# PBC-1.net
KiCad netlist of a schematic drawn in EAGLE
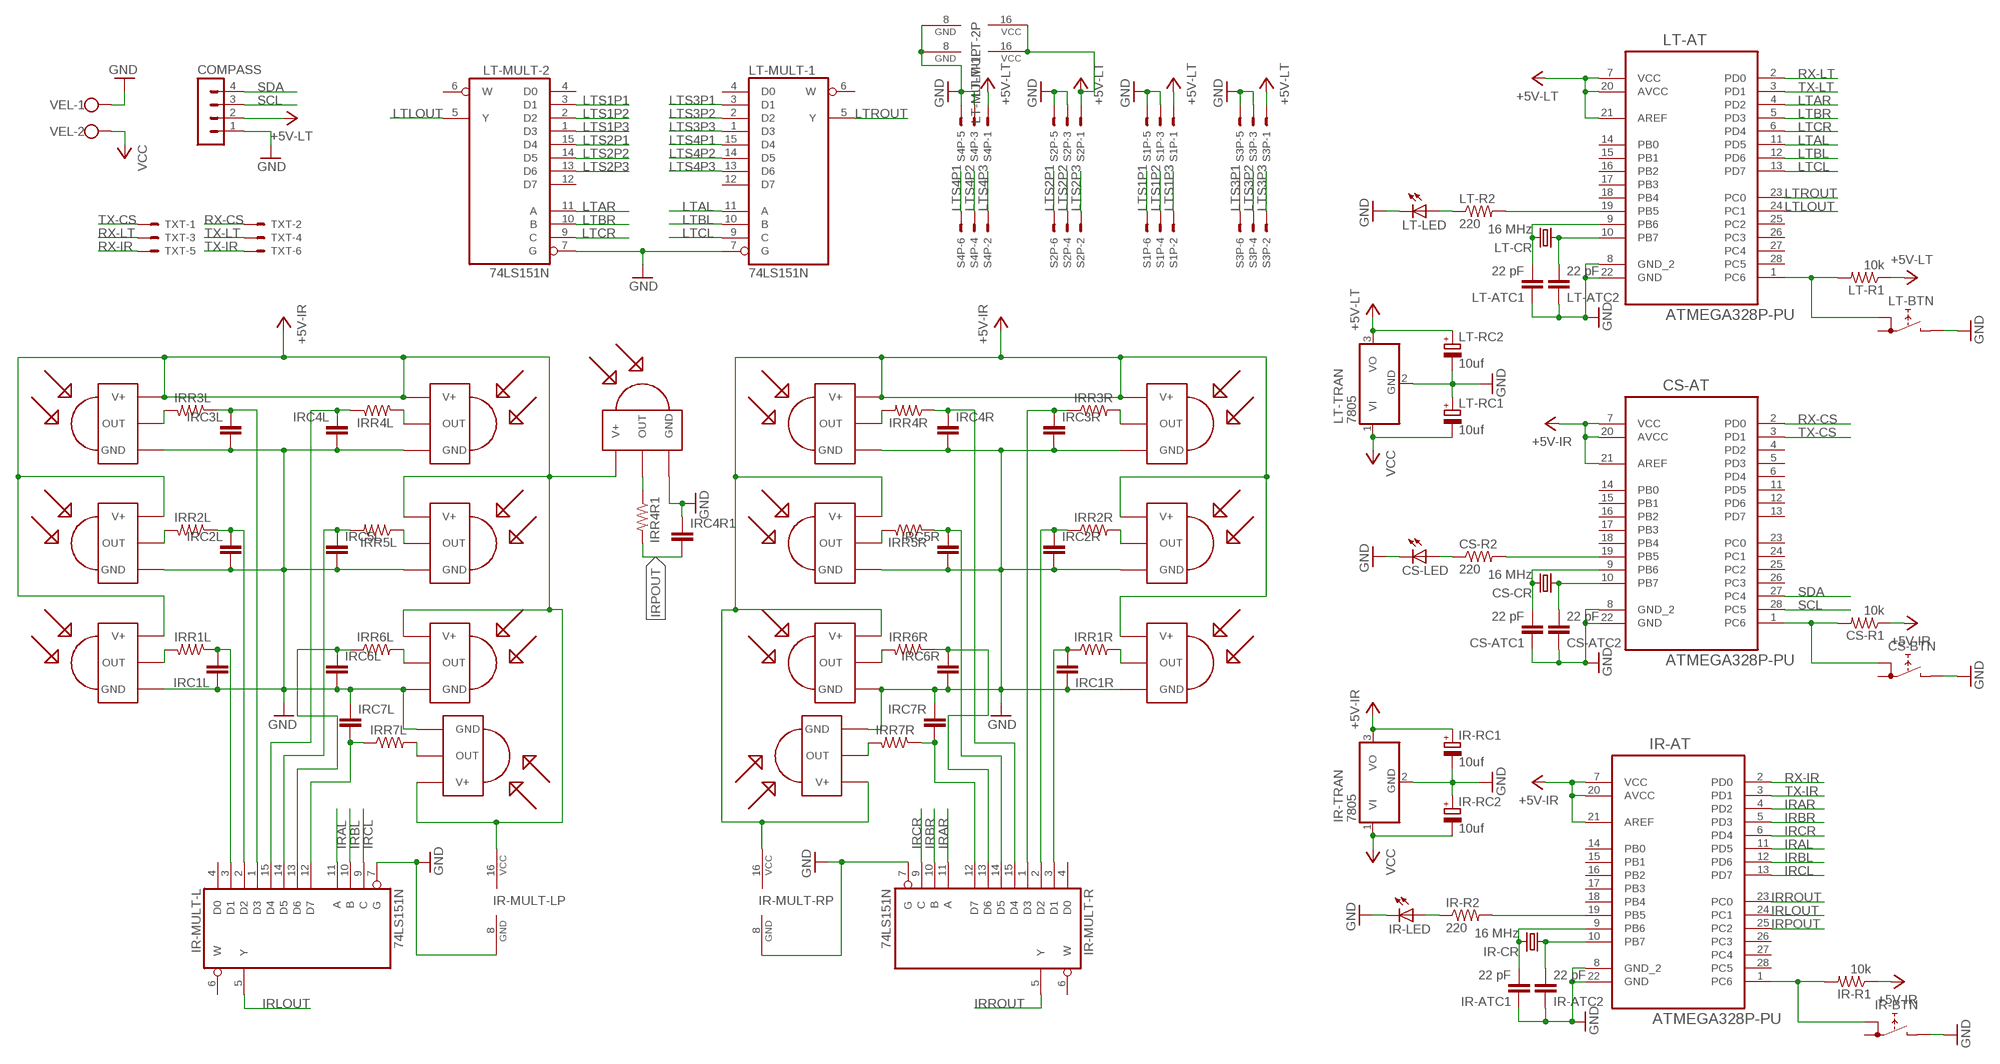
[diagram p0: schematic, sheet 1]

(export (version "E")
  (design (tool "Eeschema 10.0.6"))
  (components
    (comp (ref "COMPASS")
      (value "MA04-1")
      (footprint "eagle-import:MA04-1")
      (libsource (lib "eagle-import") (part "MA04-1"))
    )
    (comp (ref "CS-AT")
      (value "ATMEGA328P-PU")
      (footprint "eagle-import:DIP254P762X457-28")
      (libsource (lib "eagle-import") (part "ATMEGA328P-PU"))
    )
    (comp (ref "CS-ATC1")
      (value "22 pF")
      (footprint "eagle-import:C2.5-3")
      (libsource (lib "eagle-import") (part "C2,5-3"))
    )
    (comp (ref "CS-ATC2")
      (value "22 pF")
      (footprint "eagle-import:C2.5-3")
      (libsource (lib "eagle-import") (part "C2,5-3"))
    )
    (comp (ref "CS-BTN")
      (value "RDT1034")
      (footprint "eagle-import:RDT1034")
      (libsource (lib "eagle-import") (part "RDT1034"))
    )
    (comp (ref "CS-CR")
      (value "16 MHz")
      (footprint "eagle-import:HC49U70")
      (libsource (lib "eagle-import") (part "CRYSTALHC49U70"))
    )
    (comp (ref "CS-LED")
      (value "LED5MM")
      (footprint "eagle-import:LED5MM")
      (libsource (lib "eagle-import") (part "LED5MM"))
    )
    (comp (ref "CS-R1")
      (value "10k")
      (footprint "eagle-import:0204_7")
      (libsource (lib "eagle-import") (part "R-US_0204/7"))
    )
    (comp (ref "CS-R2")
      (value "220")
      (footprint "eagle-import:0204_7")
      (libsource (lib "eagle-import") (part "R-US_0204/7"))
    )
    (comp (ref "IR-AT")
      (value "ATMEGA328P-PU")
      (footprint "eagle-import:DIP254P762X457-28")
      (libsource (lib "eagle-import") (part "ATMEGA328P-PU"))
    )
    (comp (ref "IR-ATC1")
      (value "22 pF")
      (footprint "eagle-import:C2.5-3")
      (libsource (lib "eagle-import") (part "C2,5-3"))
    )
    (comp (ref "IR-ATC2")
      (value "22 pF")
      (footprint "eagle-import:C2.5-3")
      (libsource (lib "eagle-import") (part "C2,5-3"))
    )
    (comp (ref "IR-BTN")
      (value "RDT1034")
      (footprint "eagle-import:RDT1034")
      (libsource (lib "eagle-import") (part "RDT1034"))
    )
    (comp (ref "IR-CR")
      (value "16 MHz")
      (footprint "eagle-import:HC49U70")
      (libsource (lib "eagle-import") (part "CRYSTALHC49U70"))
    )
    (comp (ref "IR-LED")
      (value "LED5MM")
      (footprint "eagle-import:LED5MM")
      (libsource (lib "eagle-import") (part "LED5MM"))
    )
    (comp (ref "IR-MULT-L")
      (value "74LS151N")
      (footprint "eagle-import:DIL16")
      (libsource (lib "eagle-import") (part "74151NLS"))
    )
    (comp (ref "IR-MULT-R")
      (value "74LS151N")
      (footprint "eagle-import:DIL16")
      (libsource (lib "eagle-import") (part "74151NLS"))
    )
    (comp (ref "IR-R1")
      (value "10k")
      (footprint "eagle-import:0204_7")
      (libsource (lib "eagle-import") (part "R-US_0204/7"))
    )
    (comp (ref "IR-R2")
      (value "220")
      (footprint "eagle-import:0204_7")
      (libsource (lib "eagle-import") (part "R-US_0204/7"))
    )
    (comp (ref "IR-RC1")
      (value "10uf")
      (footprint "eagle-import:TT5D9")
      (libsource (lib "eagle-import") (part "CPOL-EUTT5D9"))
    )
    (comp (ref "IR-RC2")
      (value "10uf")
      (footprint "eagle-import:TT5D9")
      (libsource (lib "eagle-import") (part "CPOL-EUTT5D9"))
    )
    (comp (ref "IR-TRAN")
      (value "7805")
      (footprint "eagle-import:TO220H")
      (libsource (lib "eagle-import") (part "78T05"))
    )
    (comp (ref "IRC1L")
      (value "C-EU025-024X044")
      (footprint "eagle-import:C025-024X044")
      (libsource (lib "eagle-import") (part "C-EU025-024X044"))
    )
    (comp (ref "IRC1R")
      (value "C-EU025-024X044")
      (footprint "eagle-import:C025-024X044")
      (libsource (lib "eagle-import") (part "C-EU025-024X044"))
    )
    (comp (ref "IRC2L")
      (value "C-EU025-024X044")
      (footprint "eagle-import:C025-024X044")
      (libsource (lib "eagle-import") (part "C-EU025-024X044"))
    )
    (comp (ref "IRC2R")
      (value "C-EU025-024X044")
      (footprint "eagle-import:C025-024X044")
      (libsource (lib "eagle-import") (part "C-EU025-024X044"))
    )
    (comp (ref "IRC3L")
      (value "C-EU025-024X044")
      (footprint "eagle-import:C025-024X044")
      (libsource (lib "eagle-import") (part "C-EU025-024X044"))
    )
    (comp (ref "IRC3R")
      (value "C-EU025-024X044")
      (footprint "eagle-import:C025-024X044")
      (libsource (lib "eagle-import") (part "C-EU025-024X044"))
    )
    (comp (ref "IRC4L")
      (value "C-EU025-024X044")
      (footprint "eagle-import:C025-024X044")
      (libsource (lib "eagle-import") (part "C-EU025-024X044"))
    )
    (comp (ref "IRC4R")
      (value "C-EU025-024X044")
      (footprint "eagle-import:C025-024X044")
      (libsource (lib "eagle-import") (part "C-EU025-024X044"))
    )
    (comp (ref "IRC4R1")
      (value "C-EU025-024X044")
      (footprint "eagle-import:C025-024X044")
      (libsource (lib "eagle-import") (part "C-EU025-024X044"))
    )
    (comp (ref "IRC5L")
      (value "C-EU025-024X044")
      (footprint "eagle-import:C025-024X044")
      (libsource (lib "eagle-import") (part "C-EU025-024X044"))
    )
    (comp (ref "IRC5R")
      (value "C-EU025-024X044")
      (footprint "eagle-import:C025-024X044")
      (libsource (lib "eagle-import") (part "C-EU025-024X044"))
    )
    (comp (ref "IRC6L")
      (value "C-EU025-024X044")
      (footprint "eagle-import:C025-024X044")
      (libsource (lib "eagle-import") (part "C-EU025-024X044"))
    )
    (comp (ref "IRC6R")
      (value "C-EU025-024X044")
      (footprint "eagle-import:C025-024X044")
      (libsource (lib "eagle-import") (part "C-EU025-024X044"))
    )
    (comp (ref "IRC7L")
      (value "C-EU025-024X044")
      (footprint "eagle-import:C025-024X044")
      (libsource (lib "eagle-import") (part "C-EU025-024X044"))
    )
    (comp (ref "IRC7R")
      (value "C-EU025-024X044")
      (footprint "eagle-import:C025-024X044")
      (libsource (lib "eagle-import") (part "C-EU025-024X044"))
    )
    (comp (ref "IRD1L")
      (value "TSOP2240")
      (footprint "eagle-import:TSOP18XX")
      (libsource (lib "eagle-import") (part "TSOP1840"))
    )
    (comp (ref "IRD1R")
      (value "TSOP2240")
      (footprint "eagle-import:TSOP18XX")
      (libsource (lib "eagle-import") (part "TSOP1840"))
    )
    (comp (ref "IRD2L")
      (value "TSOP2240")
      (footprint "eagle-import:TSOP18XX")
      (libsource (lib "eagle-import") (part "TSOP1840"))
    )
    (comp (ref "IRD2R")
      (value "TSOP2240")
      (footprint "eagle-import:TSOP18XX")
      (libsource (lib "eagle-import") (part "TSOP1840"))
    )
    (comp (ref "IRD3L")
      (value "TSOP2240")
      (footprint "eagle-import:TSOP18XX")
      (libsource (lib "eagle-import") (part "TSOP1840"))
    )
    (comp (ref "IRD3R")
      (value "TSOP1840")
      (footprint "eagle-import:TSOP18XX")
      (libsource (lib "eagle-import") (part "TSOP1840"))
    )
    (comp (ref "IRD4L")
      (value "TSOP2240")
      (footprint "eagle-import:TSOP18XX")
      (libsource (lib "eagle-import") (part "TSOP1840"))
    )
    (comp (ref "IRD4R")
      (value "TSOP2240")
      (footprint "eagle-import:TSOP18XX")
      (libsource (lib "eagle-import") (part "TSOP1840"))
    )
    (comp (ref "IRD5L")
      (value "TSOP2240")
      (footprint "eagle-import:TSOP18XX")
      (libsource (lib "eagle-import") (part "TSOP1840"))
    )
    (comp (ref "IRD5R")
      (value "TSOP2240")
      (footprint "eagle-import:TSOP18XX")
      (libsource (lib "eagle-import") (part "TSOP1840"))
    )
    (comp (ref "IRD6L")
      (value "TSOP2240")
      (footprint "eagle-import:TSOP18XX")
      (libsource (lib "eagle-import") (part "TSOP1840"))
    )
    (comp (ref "IRD6R")
      (value "TSOP2240")
      (footprint "eagle-import:TSOP18XX")
      (libsource (lib "eagle-import") (part "TSOP1840"))
    )
    (comp (ref "IRD7L")
      (value "TSOP2240")
      (footprint "eagle-import:TSOP18XX")
      (libsource (lib "eagle-import") (part "TSOP1840"))
    )
    (comp (ref "IRD7R")
      (value "TSOP2240")
      (footprint "eagle-import:TSOP18XX")
      (libsource (lib "eagle-import") (part "TSOP1840"))
    )
    (comp (ref "IRDP")
      (value "TSOP2240")
      (footprint "eagle-import:TSOP18XX")
      (libsource (lib "eagle-import") (part "TSOP1840"))
    )
    (comp (ref "IRR1L")
      (value "R-US_0204/5")
      (footprint "eagle-import:0204_5")
      (libsource (lib "eagle-import") (part "R-US_0204/5"))
    )
    (comp (ref "IRR1R")
      (value "R-US_0204/5")
      (footprint "eagle-import:0204_5")
      (libsource (lib "eagle-import") (part "R-US_0204/5"))
    )
    (comp (ref "IRR2L")
      (value "R-US_0204/5")
      (footprint "eagle-import:0204_5")
      (libsource (lib "eagle-import") (part "R-US_0204/5"))
    )
    (comp (ref "IRR2R")
      (value "R-US_0204/5")
      (footprint "eagle-import:0204_5")
      (libsource (lib "eagle-import") (part "R-US_0204/5"))
    )
    (comp (ref "IRR3L")
      (value "R-US_0204/5")
      (footprint "eagle-import:0204_5")
      (libsource (lib "eagle-import") (part "R-US_0204/5"))
    )
    (comp (ref "IRR3R")
      (value "R-US_0204/5")
      (footprint "eagle-import:0204_5")
      (libsource (lib "eagle-import") (part "R-US_0204/5"))
    )
    (comp (ref "IRR4L")
      (value "R-US_0204/5")
      (footprint "eagle-import:0204_5")
      (libsource (lib "eagle-import") (part "R-US_0204/5"))
    )
    (comp (ref "IRR4R")
      (value "R-US_0204/5")
      (footprint "eagle-import:0204_5")
      (libsource (lib "eagle-import") (part "R-US_0204/5"))
    )
    (comp (ref "IRR4R1")
      (value "R-US_0204/5")
      (footprint "eagle-import:0204_5")
      (libsource (lib "eagle-import") (part "R-US_0204/5"))
    )
    (comp (ref "IRR5L")
      (value "R-US_0204/5")
      (footprint "eagle-import:0204_5")
      (libsource (lib "eagle-import") (part "R-US_0204/5"))
    )
    (comp (ref "IRR5R")
      (value "R-US_0204/5")
      (footprint "eagle-import:0204_5")
      (libsource (lib "eagle-import") (part "R-US_0204/5"))
    )
    (comp (ref "IRR6L")
      (value "R-US_0204/5")
      (footprint "eagle-import:0204_5")
      (libsource (lib "eagle-import") (part "R-US_0204/5"))
    )
    (comp (ref "IRR6R")
      (value "R-US_0204/5")
      (footprint "eagle-import:0204_5")
      (libsource (lib "eagle-import") (part "R-US_0204/5"))
    )
    (comp (ref "IRR7L")
      (value "R-US_0204/5")
      (footprint "eagle-import:0204_5")
      (libsource (lib "eagle-import") (part "R-US_0204/5"))
    )
    (comp (ref "IRR7R")
      (value "R-US_0204/5")
      (footprint "eagle-import:0204_5")
      (libsource (lib "eagle-import") (part "R-US_0204/5"))
    )
    (comp (ref "LT-AT")
      (value "ATMEGA328P-PU")
      (footprint "eagle-import:DIP254P762X457-28")
      (libsource (lib "eagle-import") (part "ATMEGA328P-PU"))
    )
    (comp (ref "LT-ATC1")
      (value "22 pF")
      (footprint "eagle-import:C2.5-3")
      (libsource (lib "eagle-import") (part "C2,5-3"))
    )
    (comp (ref "LT-ATC2")
      (value "22 pF")
      (footprint "eagle-import:C2.5-3")
      (libsource (lib "eagle-import") (part "C2,5-3"))
    )
    (comp (ref "LT-BTN")
      (value "RDT1034")
      (footprint "eagle-import:RDT1034")
      (libsource (lib "eagle-import") (part "RDT1034"))
    )
    (comp (ref "LT-CR")
      (value "16 MHz")
      (footprint "eagle-import:HC49U70")
      (libsource (lib "eagle-import") (part "CRYSTALHC49U70"))
    )
    (comp (ref "LT-LED")
      (value "LED5MM")
      (footprint "eagle-import:LED5MM")
      (libsource (lib "eagle-import") (part "LED5MM"))
    )
    (comp (ref "LT-MULT-1")
      (value "74LS151N")
      (footprint "eagle-import:DIL16")
      (libsource (lib "eagle-import") (part "74151NLS"))
    )
    (comp (ref "LT-MULT-2")
      (value "74LS151N")
      (footprint "eagle-import:DIL16")
      (libsource (lib "eagle-import") (part "74151NLS"))
    )
    (comp (ref "LT-R1")
      (value "10k")
      (footprint "eagle-import:0204_7")
      (libsource (lib "eagle-import") (part "R-US_0204/7"))
    )
    (comp (ref "LT-R2")
      (value "220")
      (footprint "eagle-import:0204_7")
      (libsource (lib "eagle-import") (part "R-US_0204/7"))
    )
    (comp (ref "LT-RC1")
      (value "10uf")
      (footprint "eagle-import:TT5D9")
      (libsource (lib "eagle-import") (part "CPOL-EUTT5D9"))
    )
    (comp (ref "LT-RC2")
      (value "10uf")
      (footprint "eagle-import:TT5D9")
      (libsource (lib "eagle-import") (part "CPOL-EUTT5D9"))
    )
    (comp (ref "LT-TRAN")
      (value "7805")
      (footprint "eagle-import:TO220H")
      (libsource (lib "eagle-import") (part "78T05"))
    )
    (comp (ref "S1P")
      (value "332-06")
      (footprint "eagle-import:332-06")
      (libsource (lib "eagle-import") (part "332-06"))
    )
    (comp (ref "S2P")
      (value "332-06")
      (footprint "eagle-import:332-06")
      (libsource (lib "eagle-import") (part "332-06"))
    )
    (comp (ref "S3P")
      (value "332-06")
      (footprint "eagle-import:332-06")
      (libsource (lib "eagle-import") (part "332-06"))
    )
    (comp (ref "S4P")
      (value "332-06")
      (footprint "eagle-import:332-06")
      (libsource (lib "eagle-import") (part "332-06"))
    )
    (comp (ref "TXT")
      (value "87758-0616")
      (footprint "eagle-import:87758-0616")
      (libsource (lib "eagle-import") (part "87758-0616"))
    )
    (comp (ref "VEL")
      (value "W237-102")
      (footprint "eagle-import:W237-102")
      (fields (field (name "MPN") "237-102"))
      (libsource (lib "eagle-import") (part "W237-102"))
    )
  )
  (nets
    (net (code "1") (name "+5V-IR") (class "Default")
      (node (ref "CS-AT") (pin "20") (pinfunction "AVCC_20") (pintype "power_in"))
      (node (ref "CS-AT") (pin "21") (pinfunction "AREF_21") (pintype "input"))
      (node (ref "CS-AT") (pin "7") (pinfunction "VCC_7") (pintype "power_in"))
      (node (ref "CS-R1") (pin "1") (pinfunction "1_1") (pintype "passive"))
      (node (ref "IR-AT") (pin "20") (pinfunction "AVCC_20") (pintype "power_in"))
      (node (ref "IR-AT") (pin "21") (pinfunction "AREF_21") (pintype "input"))
      (node (ref "IR-AT") (pin "7") (pinfunction "VCC_7") (pintype "power_in"))
      (node (ref "IR-MULT-L") (pin "16") (pinfunction "VCC_16") (pintype "power_in"))
      (node (ref "IR-MULT-R") (pin "16") (pinfunction "VCC_16") (pintype "power_in"))
      (node (ref "IR-R1") (pin "1") (pinfunction "1_1") (pintype "passive"))
      (node (ref "IR-RC1") (pin "+") (pinfunction "+_+") (pintype "passive"))
      (node (ref "IR-TRAN") (pin "3") (pinfunction "VO_3") (pintype "passive"))
      (node (ref "IRD1L") (pin "VCC") (pinfunction "V+_VCC") (pintype "bidirectional"))
      (node (ref "IRD1R") (pin "VCC") (pinfunction "V+_VCC") (pintype "bidirectional"))
      (node (ref "IRD2L") (pin "VCC") (pinfunction "V+_VCC") (pintype "bidirectional"))
      (node (ref "IRD2R") (pin "VCC") (pinfunction "V+_VCC") (pintype "bidirectional"))
      (node (ref "IRD3L") (pin "VCC") (pinfunction "V+_VCC") (pintype "bidirectional"))
      (node (ref "IRD3R") (pin "VCC") (pinfunction "V+_VCC") (pintype "bidirectional"))
      (node (ref "IRD4L") (pin "VCC") (pinfunction "V+_VCC") (pintype "bidirectional"))
      (node (ref "IRD4R") (pin "VCC") (pinfunction "V+_VCC") (pintype "bidirectional"))
      (node (ref "IRD5L") (pin "VCC") (pinfunction "V+_VCC") (pintype "bidirectional"))
      (node (ref "IRD5R") (pin "VCC") (pinfunction "V+_VCC") (pintype "bidirectional"))
      (node (ref "IRD6L") (pin "VCC") (pinfunction "V+_VCC") (pintype "bidirectional"))
      (node (ref "IRD6R") (pin "VCC") (pinfunction "V+_VCC") (pintype "bidirectional"))
      (node (ref "IRD7L") (pin "VCC") (pinfunction "V+_VCC") (pintype "bidirectional"))
      (node (ref "IRD7R") (pin "VCC") (pinfunction "V+_VCC") (pintype "bidirectional"))
      (node (ref "IRDP") (pin "VCC") (pinfunction "V+_VCC") (pintype "bidirectional"))
    )
    (net (code "2") (name "+5V-LT") (class "Default")
      (node (ref "COMPASS") (pin "2") (pinfunction "2_2") (pintype "passive"))
      (node (ref "LT-AT") (pin "20") (pinfunction "AVCC_20") (pintype "power_in"))
      (node (ref "LT-AT") (pin "21") (pinfunction "AREF_21") (pintype "input"))
      (node (ref "LT-AT") (pin "7") (pinfunction "VCC_7") (pintype "power_in"))
      (node (ref "LT-MULT-1") (pin "16") (pinfunction "VCC_16") (pintype "power_in"))
      (node (ref "LT-MULT-2") (pin "16") (pinfunction "VCC_16") (pintype "power_in"))
      (node (ref "LT-R1") (pin "1") (pinfunction "1_1") (pintype "passive"))
      (node (ref "LT-RC2") (pin "+") (pinfunction "+_+") (pintype "passive"))
      (node (ref "LT-TRAN") (pin "3") (pinfunction "VO_3") (pintype "passive"))
      (node (ref "S1P") (pin "1") (pinfunction "S_1") (pintype "passive"))
      (node (ref "S2P") (pin "1") (pinfunction "S_1") (pintype "passive"))
      (node (ref "S3P") (pin "1") (pinfunction "S_1") (pintype "passive"))
      (node (ref "S4P") (pin "1") (pinfunction "S_1") (pintype "passive"))
    )
    (net (code "3") (name "/IRAL") (class "Default")
      (node (ref "IR-AT") (pin "11") (pinfunction "PD5_11") (pintype "bidirectional"))
      (node (ref "IR-MULT-L") (pin "11") (pinfunction "A_11") (pintype "input"))
    )
    (net (code "4") (name "/IRAR") (class "Default")
      (node (ref "IR-AT") (pin "4") (pinfunction "PD2_4") (pintype "bidirectional"))
      (node (ref "IR-MULT-R") (pin "11") (pinfunction "A_11") (pintype "input"))
    )
    (net (code "5") (name "/IRBL") (class "Default")
      (node (ref "IR-AT") (pin "12") (pinfunction "PD6_12") (pintype "bidirectional"))
      (node (ref "IR-MULT-L") (pin "10") (pinfunction "B_10") (pintype "input"))
    )
    (net (code "6") (name "/IRBR") (class "Default")
      (node (ref "IR-AT") (pin "5") (pinfunction "PD3_5") (pintype "bidirectional"))
      (node (ref "IR-MULT-R") (pin "10") (pinfunction "B_10") (pintype "input"))
    )
    (net (code "7") (name "/IRCL") (class "Default")
      (node (ref "IR-AT") (pin "13") (pinfunction "PD7_13") (pintype "bidirectional"))
      (node (ref "IR-MULT-L") (pin "9") (pinfunction "C_9") (pintype "input"))
    )
    (net (code "8") (name "/IRCR") (class "Default")
      (node (ref "IR-AT") (pin "6") (pinfunction "PD4_6") (pintype "bidirectional"))
      (node (ref "IR-MULT-R") (pin "9") (pinfunction "C_9") (pintype "input"))
    )
    (net (code "9") (name "/IRLOUT") (class "Default")
      (node (ref "IR-AT") (pin "24") (pinfunction "PC1_24") (pintype "bidirectional"))
      (node (ref "IR-MULT-L") (pin "5") (pinfunction "Y_5") (pintype "output"))
    )
    (net (code "10") (name "/IRROUT") (class "Default")
      (node (ref "IR-AT") (pin "23") (pinfunction "PC0_23") (pintype "bidirectional"))
      (node (ref "IR-MULT-R") (pin "5") (pinfunction "Y_5") (pintype "output"))
    )
    (net (code "11") (name "/LTAL") (class "Default")
      (node (ref "LT-AT") (pin "11") (pinfunction "PD5_11") (pintype "bidirectional"))
      (node (ref "LT-MULT-1") (pin "11") (pinfunction "A_11") (pintype "input"))
    )
    (net (code "12") (name "/LTAR") (class "Default")
      (node (ref "LT-AT") (pin "4") (pinfunction "PD2_4") (pintype "bidirectional"))
      (node (ref "LT-MULT-2") (pin "11") (pinfunction "A_11") (pintype "input"))
    )
    (net (code "13") (name "/LTBL") (class "Default")
      (node (ref "LT-AT") (pin "12") (pinfunction "PD6_12") (pintype "bidirectional"))
      (node (ref "LT-MULT-1") (pin "10") (pinfunction "B_10") (pintype "input"))
    )
    (net (code "14") (name "/LTBR") (class "Default")
      (node (ref "LT-AT") (pin "5") (pinfunction "PD3_5") (pintype "bidirectional"))
      (node (ref "LT-MULT-2") (pin "10") (pinfunction "B_10") (pintype "input"))
    )
    (net (code "15") (name "/LTCL") (class "Default")
      (node (ref "LT-AT") (pin "13") (pinfunction "PD7_13") (pintype "bidirectional"))
      (node (ref "LT-MULT-1") (pin "9") (pinfunction "C_9") (pintype "input"))
    )
    (net (code "16") (name "/LTCR") (class "Default")
      (node (ref "LT-AT") (pin "6") (pinfunction "PD4_6") (pintype "bidirectional"))
      (node (ref "LT-MULT-2") (pin "9") (pinfunction "C_9") (pintype "input"))
    )
    (net (code "17") (name "/LTLOUT") (class "Default")
      (node (ref "LT-AT") (pin "24") (pinfunction "PC1_24") (pintype "bidirectional"))
      (node (ref "LT-MULT-2") (pin "5") (pinfunction "Y_5") (pintype "output"))
    )
    (net (code "18") (name "/LTROUT") (class "Default")
      (node (ref "LT-AT") (pin "23") (pinfunction "PC0_23") (pintype "bidirectional"))
      (node (ref "LT-MULT-1") (pin "5") (pinfunction "Y_5") (pintype "output"))
    )
    (net (code "19") (name "/LTS1P1") (class "Default")
      (node (ref "LT-MULT-2") (pin "3") (pinfunction "D1_3") (pintype "input"))
      (node (ref "S1P") (pin "6") (pinfunction "S_6") (pintype "passive"))
    )
    (net (code "20") (name "/LTS1P2") (class "Default")
      (node (ref "LT-MULT-2") (pin "2") (pinfunction "D2_2") (pintype "input"))
      (node (ref "S1P") (pin "4") (pinfunction "S_4") (pintype "passive"))
    )
    (net (code "21") (name "/LTS1P3") (class "Default")
      (node (ref "LT-MULT-2") (pin "1") (pinfunction "D3_1") (pintype "input"))
      (node (ref "S1P") (pin "2") (pinfunction "S_2") (pintype "passive"))
    )
    (net (code "22") (name "/LTS2P1") (class "Default")
      (node (ref "LT-MULT-2") (pin "15") (pinfunction "D4_15") (pintype "input"))
      (node (ref "S2P") (pin "6") (pinfunction "S_6") (pintype "passive"))
    )
    (net (code "23") (name "/LTS2P2") (class "Default")
      (node (ref "LT-MULT-2") (pin "14") (pinfunction "D5_14") (pintype "input"))
      (node (ref "S2P") (pin "4") (pinfunction "S_4") (pintype "passive"))
    )
    (net (code "24") (name "/LTS2P3") (class "Default")
      (node (ref "LT-MULT-2") (pin "13") (pinfunction "D6_13") (pintype "input"))
      (node (ref "S2P") (pin "2") (pinfunction "S_2") (pintype "passive"))
    )
    (net (code "25") (name "/LTS3P1") (class "Default")
      (node (ref "LT-MULT-1") (pin "3") (pinfunction "D1_3") (pintype "input"))
      (node (ref "S3P") (pin "6") (pinfunction "S_6") (pintype "passive"))
    )
    (net (code "26") (name "/LTS3P2") (class "Default")
      (node (ref "LT-MULT-1") (pin "2") (pinfunction "D2_2") (pintype "input"))
      (node (ref "S3P") (pin "4") (pinfunction "S_4") (pintype "passive"))
    )
    (net (code "27") (name "/LTS3P3") (class "Default")
      (node (ref "LT-MULT-1") (pin "1") (pinfunction "D3_1") (pintype "input"))
      (node (ref "S3P") (pin "2") (pinfunction "S_2") (pintype "passive"))
    )
    (net (code "28") (name "/LTS4P1") (class "Default")
      (node (ref "LT-MULT-1") (pin "15") (pinfunction "D4_15") (pintype "input"))
      (node (ref "S4P") (pin "6") (pinfunction "S_6") (pintype "passive"))
    )
    (net (code "29") (name "/LTS4P2") (class "Default")
      (node (ref "LT-MULT-1") (pin "14") (pinfunction "D5_14") (pintype "input"))
      (node (ref "S4P") (pin "4") (pinfunction "S_4") (pintype "passive"))
    )
    (net (code "30") (name "/LTS4P3") (class "Default")
      (node (ref "LT-MULT-1") (pin "13") (pinfunction "D6_13") (pintype "input"))
      (node (ref "S4P") (pin "2") (pinfunction "S_2") (pintype "passive"))
    )
    (net (code "31") (name "/RX-CS") (class "Default")
      (node (ref "CS-AT") (pin "2") (pinfunction "PD0_2") (pintype "bidirectional"))
      (node (ref "TXT") (pin "2") (pinfunction "S_2") (pintype "passive"))
    )
    (net (code "32") (name "/RX-IR") (class "Default")
      (node (ref "IR-AT") (pin "2") (pinfunction "PD0_2") (pintype "bidirectional"))
      (node (ref "TXT") (pin "5") (pinfunction "S_5") (pintype "passive"))
    )
    (net (code "33") (name "/RX-LT") (class "Default")
      (node (ref "LT-AT") (pin "2") (pinfunction "PD0_2") (pintype "bidirectional"))
      (node (ref "TXT") (pin "3") (pinfunction "S_3") (pintype "passive"))
    )
    (net (code "34") (name "/SCL") (class "Default")
      (node (ref "COMPASS") (pin "3") (pinfunction "3_3") (pintype "passive"))
      (node (ref "CS-AT") (pin "28") (pinfunction "PC5_28") (pintype "bidirectional"))
    )
    (net (code "35") (name "/SDA") (class "Default")
      (node (ref "COMPASS") (pin "4") (pinfunction "4_4") (pintype "passive"))
      (node (ref "CS-AT") (pin "27") (pinfunction "PC4_27") (pintype "bidirectional"))
    )
    (net (code "36") (name "/TX-CS") (class "Default")
      (node (ref "CS-AT") (pin "3") (pinfunction "PD1_3") (pintype "bidirectional"))
      (node (ref "TXT") (pin "1") (pinfunction "S_1") (pintype "passive"))
    )
    (net (code "37") (name "/TX-IR") (class "Default")
      (node (ref "IR-AT") (pin "3") (pinfunction "PD1_3") (pintype "bidirectional"))
      (node (ref "TXT") (pin "6") (pinfunction "S_6") (pintype "passive"))
    )
    (net (code "38") (name "/TX-LT") (class "Default")
      (node (ref "LT-AT") (pin "3") (pinfunction "PD1_3") (pintype "bidirectional"))
      (node (ref "TXT") (pin "4") (pinfunction "S_4") (pintype "passive"))
    )
    (net (code "39") (name "GND") (class "Default")
      (node (ref "COMPASS") (pin "1") (pinfunction "1_1") (pintype "passive"))
      (node (ref "CS-AT") (pin "22") (pinfunction "GND_22") (pintype "passive"))
      (node (ref "CS-AT") (pin "8") (pinfunction "GND_2_8") (pintype "passive"))
      (node (ref "CS-ATC1") (pin "1") (pinfunction "1_1") (pintype "passive"))
      (node (ref "CS-ATC2") (pin "1") (pinfunction "1_1") (pintype "passive"))
      (node (ref "CS-BTN") (pin "B") (pinfunction "B_B") (pintype "passive"))
      (node (ref "CS-LED") (pin "K") (pinfunction "C_K") (pintype "passive"))
      (node (ref "IR-AT") (pin "22") (pinfunction "GND_22") (pintype "passive"))
      (node (ref "IR-AT") (pin "8") (pinfunction "GND_2_8") (pintype "passive"))
      (node (ref "IR-ATC1") (pin "1") (pinfunction "1_1") (pintype "passive"))
      (node (ref "IR-ATC2") (pin "1") (pinfunction "1_1") (pintype "passive"))
      (node (ref "IR-BTN") (pin "B") (pinfunction "B_B") (pintype "passive"))
      (node (ref "IR-LED") (pin "K") (pinfunction "C_K") (pintype "passive"))
      (node (ref "IR-MULT-L") (pin "7") (pinfunction "G_7") (pintype "input"))
      (node (ref "IR-MULT-L") (pin "8") (pinfunction "GND_8") (pintype "power_in"))
      (node (ref "IR-MULT-R") (pin "7") (pinfunction "G_7") (pintype "input"))
      (node (ref "IR-MULT-R") (pin "8") (pinfunction "GND_8") (pintype "power_in"))
      (node (ref "IR-RC1") (pin "-") (pinfunction "-_-") (pintype "passive"))
      (node (ref "IR-RC2") (pin "+") (pinfunction "+_+") (pintype "passive"))
      (node (ref "IR-TRAN") (pin "2") (pinfunction "GND_2") (pintype "passive"))
      (node (ref "IRC1L") (pin "1") (pinfunction "1_1") (pintype "passive"))
      (node (ref "IRC1R") (pin "1") (pinfunction "1_1") (pintype "passive"))
      (node (ref "IRC2L") (pin "2") (pinfunction "2_2") (pintype "passive"))
      (node (ref "IRC2R") (pin "2") (pinfunction "2_2") (pintype "passive"))
      (node (ref "IRC3L") (pin "2") (pinfunction "2_2") (pintype "passive"))
      (node (ref "IRC3R") (pin "2") (pinfunction "2_2") (pintype "passive"))
      (node (ref "IRC4L") (pin "2") (pinfunction "2_2") (pintype "passive"))
      (node (ref "IRC4R") (pin "2") (pinfunction "2_2") (pintype "passive"))
      (node (ref "IRC4R1") (pin "1") (pinfunction "1_1") (pintype "passive"))
      (node (ref "IRC5L") (pin "2") (pinfunction "2_2") (pintype "passive"))
      (node (ref "IRC5R") (pin "2") (pinfunction "2_2") (pintype "passive"))
      (node (ref "IRC6L") (pin "2") (pinfunction "2_2") (pintype "passive"))
      (node (ref "IRC6R") (pin "2") (pinfunction "2_2") (pintype "passive"))
      (node (ref "IRC7L") (pin "1") (pinfunction "1_1") (pintype "passive"))
      (node (ref "IRC7R") (pin "1") (pinfunction "1_1") (pintype "passive"))
      (node (ref "IRD1L") (pin "GND") (pinfunction "GND_GND") (pintype "bidirectional"))
      (node (ref "IRD1R") (pin "GND") (pinfunction "GND_GND") (pintype "bidirectional"))
      (node (ref "IRD2L") (pin "GND") (pinfunction "GND_GND") (pintype "bidirectional"))
      (node (ref "IRD2R") (pin "GND") (pinfunction "GND_GND") (pintype "bidirectional"))
      (node (ref "IRD3L") (pin "GND") (pinfunction "GND_GND") (pintype "bidirectional"))
      (node (ref "IRD3R") (pin "GND") (pinfunction "GND_GND") (pintype "bidirectional"))
      (node (ref "IRD4L") (pin "GND") (pinfunction "GND_GND") (pintype "bidirectional"))
      (node (ref "IRD4R") (pin "GND") (pinfunction "GND_GND") (pintype "bidirectional"))
      (node (ref "IRD5L") (pin "GND") (pinfunction "GND_GND") (pintype "bidirectional"))
      (node (ref "IRD5R") (pin "GND") (pinfunction "GND_GND") (pintype "bidirectional"))
      (node (ref "IRD6L") (pin "GND") (pinfunction "GND_GND") (pintype "bidirectional"))
      (node (ref "IRD6R") (pin "GND") (pinfunction "GND_GND") (pintype "bidirectional"))
      (node (ref "IRD7L") (pin "GND") (pinfunction "GND_GND") (pintype "bidirectional"))
      (node (ref "IRD7R") (pin "GND") (pinfunction "GND_GND") (pintype "bidirectional"))
      (node (ref "IRDP") (pin "GND") (pinfunction "GND_GND") (pintype "bidirectional"))
      (node (ref "LT-AT") (pin "22") (pinfunction "GND_22") (pintype "passive"))
      (node (ref "LT-AT") (pin "8") (pinfunction "GND_2_8") (pintype "passive"))
      (node (ref "LT-ATC1") (pin "1") (pinfunction "1_1") (pintype "passive"))
      (node (ref "LT-ATC2") (pin "1") (pinfunction "1_1") (pintype "passive"))
      (node (ref "LT-BTN") (pin "B") (pinfunction "B_B") (pintype "passive"))
      (node (ref "LT-LED") (pin "K") (pinfunction "C_K") (pintype "passive"))
      (node (ref "LT-MULT-1") (pin "7") (pinfunction "G_7") (pintype "input"))
      (node (ref "LT-MULT-1") (pin "8") (pinfunction "GND_8") (pintype "power_in"))
      (node (ref "LT-MULT-2") (pin "7") (pinfunction "G_7") (pintype "input"))
      (node (ref "LT-MULT-2") (pin "8") (pinfunction "GND_8") (pintype "power_in"))
      (node (ref "LT-RC1") (pin "+") (pinfunction "+_+") (pintype "passive"))
      (node (ref "LT-RC2") (pin "-") (pinfunction "-_-") (pintype "passive"))
      (node (ref "LT-TRAN") (pin "2") (pinfunction "GND_2") (pintype "passive"))
      (node (ref "S1P") (pin "3") (pinfunction "S_3") (pintype "passive"))
      (node (ref "S1P") (pin "5") (pinfunction "S_5") (pintype "passive"))
      (node (ref "S2P") (pin "3") (pinfunction "S_3") (pintype "passive"))
      (node (ref "S2P") (pin "5") (pinfunction "S_5") (pintype "passive"))
      (node (ref "S3P") (pin "3") (pinfunction "S_3") (pintype "passive"))
      (node (ref "S3P") (pin "5") (pinfunction "S_5") (pintype "passive"))
      (node (ref "S4P") (pin "3") (pinfunction "S_3") (pintype "passive"))
      (node (ref "S4P") (pin "5") (pinfunction "S_5") (pintype "passive"))
      (node (ref "VEL") (pin "1") (pinfunction "KL_1") (pintype "passive"))
    )
    (net (code "40") (name "IRPOUT") (class "Default")
      (node (ref "IR-AT") (pin "25") (pinfunction "PC2_25") (pintype "bidirectional"))
      (node (ref "IRC4R1") (pin "2") (pinfunction "2_2") (pintype "passive"))
      (node (ref "IRR4R1") (pin "2") (pinfunction "2_2") (pintype "passive"))
    )
    (net (code "41") (name "Net-(CS-AT-PB5)") (class "Default")
      (node (ref "CS-AT") (pin "19") (pinfunction "PB5_19") (pintype "bidirectional"))
      (node (ref "CS-R2") (pin "2") (pinfunction "2_2") (pintype "passive"))
    )
    (net (code "42") (name "Net-(CS-AT-PB6)") (class "Default")
      (node (ref "CS-AT") (pin "9") (pinfunction "PB6_9") (pintype "bidirectional"))
      (node (ref "CS-ATC1") (pin "2") (pinfunction "2_2") (pintype "passive"))
      (node (ref "CS-CR") (pin "2") (pinfunction "2_2") (pintype "passive"))
    )
    (net (code "43") (name "Net-(CS-AT-PB7)") (class "Default")
      (node (ref "CS-AT") (pin "10") (pinfunction "PB7_10") (pintype "bidirectional"))
      (node (ref "CS-ATC2") (pin "2") (pinfunction "2_2") (pintype "passive"))
      (node (ref "CS-CR") (pin "1") (pinfunction "1_1") (pintype "passive"))
    )
    (net (code "44") (name "Net-(CS-AT-PC6)") (class "Default")
      (node (ref "CS-AT") (pin "1") (pinfunction "PC6_1") (pintype "bidirectional"))
      (node (ref "CS-BTN") (pin "A") (pinfunction "A_A") (pintype "passive"))
      (node (ref "CS-R1") (pin "2") (pinfunction "2_2") (pintype "passive"))
    )
    (net (code "45") (name "Net-(CS-LED-PadA)") (class "Default")
      (node (ref "CS-LED") (pin "A") (pinfunction "A_A") (pintype "passive"))
      (node (ref "CS-R2") (pin "1") (pinfunction "1_1") (pintype "passive"))
    )
    (net (code "46") (name "Net-(IR-AT-PB5)") (class "Default")
      (node (ref "IR-AT") (pin "19") (pinfunction "PB5_19") (pintype "bidirectional"))
      (node (ref "IR-R2") (pin "2") (pinfunction "2_2") (pintype "passive"))
    )
    (net (code "47") (name "Net-(IR-AT-PB6)") (class "Default")
      (node (ref "IR-AT") (pin "9") (pinfunction "PB6_9") (pintype "bidirectional"))
      (node (ref "IR-ATC1") (pin "2") (pinfunction "2_2") (pintype "passive"))
      (node (ref "IR-CR") (pin "2") (pinfunction "2_2") (pintype "passive"))
    )
    (net (code "48") (name "Net-(IR-AT-PB7)") (class "Default")
      (node (ref "IR-AT") (pin "10") (pinfunction "PB7_10") (pintype "bidirectional"))
      (node (ref "IR-ATC2") (pin "2") (pinfunction "2_2") (pintype "passive"))
      (node (ref "IR-CR") (pin "1") (pinfunction "1_1") (pintype "passive"))
    )
    (net (code "49") (name "Net-(IR-AT-PC6)") (class "Default")
      (node (ref "IR-AT") (pin "1") (pinfunction "PC6_1") (pintype "bidirectional"))
      (node (ref "IR-BTN") (pin "A") (pinfunction "A_A") (pintype "passive"))
      (node (ref "IR-R1") (pin "2") (pinfunction "2_2") (pintype "passive"))
    )
    (net (code "50") (name "Net-(IR-LED-PadA)") (class "Default")
      (node (ref "IR-LED") (pin "A") (pinfunction "A_A") (pintype "passive"))
      (node (ref "IR-R2") (pin "1") (pinfunction "1_1") (pintype "passive"))
    )
    (net (code "51") (name "Net-(IR-MULT-LA-D1)") (class "Default")
      (node (ref "IR-MULT-L") (pin "3") (pinfunction "D1_3") (pintype "input"))
      (node (ref "IRC1L") (pin "2") (pinfunction "2_2") (pintype "passive"))
      (node (ref "IRR1L") (pin "1") (pinfunction "1_1") (pintype "passive"))
    )
    (net (code "52") (name "Net-(IR-MULT-LA-D2)") (class "Default")
      (node (ref "IR-MULT-L") (pin "2") (pinfunction "D2_2") (pintype "input"))
      (node (ref "IRC2L") (pin "1") (pinfunction "1_1") (pintype "passive"))
      (node (ref "IRR2L") (pin "1") (pinfunction "1_1") (pintype "passive"))
    )
    (net (code "53") (name "Net-(IR-MULT-LA-D3)") (class "Default")
      (node (ref "IR-MULT-L") (pin "1") (pinfunction "D3_1") (pintype "input"))
      (node (ref "IRC3L") (pin "1") (pinfunction "1_1") (pintype "passive"))
      (node (ref "IRR3L") (pin "1") (pinfunction "1_1") (pintype "passive"))
    )
    (net (code "54") (name "Net-(IR-MULT-LA-D4)") (class "Default")
      (node (ref "IR-MULT-L") (pin "15") (pinfunction "D4_15") (pintype "input"))
      (node (ref "IRC4L") (pin "1") (pinfunction "1_1") (pintype "passive"))
      (node (ref "IRR4L") (pin "1") (pinfunction "1_1") (pintype "passive"))
    )
    (net (code "55") (name "Net-(IR-MULT-LA-D5)") (class "Default")
      (node (ref "IR-MULT-L") (pin "14") (pinfunction "D5_14") (pintype "input"))
      (node (ref "IRC5L") (pin "1") (pinfunction "1_1") (pintype "passive"))
      (node (ref "IRR5L") (pin "2") (pinfunction "2_2") (pintype "passive"))
    )
    (net (code "56") (name "Net-(IR-MULT-LA-D6)") (class "Default")
      (node (ref "IR-MULT-L") (pin "13") (pinfunction "D6_13") (pintype "input"))
      (node (ref "IRC6L") (pin "1") (pinfunction "1_1") (pintype "passive"))
      (node (ref "IRR6L") (pin "1") (pinfunction "1_1") (pintype "passive"))
    )
    (net (code "57") (name "Net-(IR-MULT-LA-D7)") (class "Default")
      (node (ref "IR-MULT-L") (pin "12") (pinfunction "D7_12") (pintype "input"))
      (node (ref "IRC7L") (pin "2") (pinfunction "2_2") (pintype "passive"))
      (node (ref "IRR7L") (pin "1") (pinfunction "1_1") (pintype "passive"))
    )
    (net (code "58") (name "Net-(IR-MULT-RA-D1)") (class "Default")
      (node (ref "IR-MULT-R") (pin "3") (pinfunction "D1_3") (pintype "input"))
      (node (ref "IRC1R") (pin "2") (pinfunction "2_2") (pintype "passive"))
      (node (ref "IRR1R") (pin "1") (pinfunction "1_1") (pintype "passive"))
    )
    (net (code "59") (name "Net-(IR-MULT-RA-D2)") (class "Default")
      (node (ref "IR-MULT-R") (pin "2") (pinfunction "D2_2") (pintype "input"))
      (node (ref "IRC2R") (pin "1") (pinfunction "1_1") (pintype "passive"))
      (node (ref "IRR2R") (pin "1") (pinfunction "1_1") (pintype "passive"))
    )
    (net (code "60") (name "Net-(IR-MULT-RA-D3)") (class "Default")
      (node (ref "IR-MULT-R") (pin "1") (pinfunction "D3_1") (pintype "input"))
      (node (ref "IRC3R") (pin "1") (pinfunction "1_1") (pintype "passive"))
      (node (ref "IRR3R") (pin "1") (pinfunction "1_1") (pintype "passive"))
    )
    (net (code "61") (name "Net-(IR-MULT-RA-D4)") (class "Default")
      (node (ref "IR-MULT-R") (pin "15") (pinfunction "D4_15") (pintype "input"))
      (node (ref "IRC4R") (pin "1") (pinfunction "1_1") (pintype "passive"))
      (node (ref "IRR4R") (pin "1") (pinfunction "1_1") (pintype "passive"))
    )
    (net (code "62") (name "Net-(IR-MULT-RA-D5)") (class "Default")
      (node (ref "IR-MULT-R") (pin "14") (pinfunction "D5_14") (pintype "input"))
      (node (ref "IRC5R") (pin "1") (pinfunction "1_1") (pintype "passive"))
      (node (ref "IRR5R") (pin "2") (pinfunction "2_2") (pintype "passive"))
    )
    (net (code "63") (name "Net-(IR-MULT-RA-D6)") (class "Default")
      (node (ref "IR-MULT-R") (pin "13") (pinfunction "D6_13") (pintype "input"))
      (node (ref "IRC6R") (pin "1") (pinfunction "1_1") (pintype "passive"))
      (node (ref "IRR6R") (pin "1") (pinfunction "1_1") (pintype "passive"))
    )
    (net (code "64") (name "Net-(IR-MULT-RA-D7)") (class "Default")
      (node (ref "IR-MULT-R") (pin "12") (pinfunction "D7_12") (pintype "input"))
      (node (ref "IRC7R") (pin "2") (pinfunction "2_2") (pintype "passive"))
      (node (ref "IRR7R") (pin "1") (pinfunction "1_1") (pintype "passive"))
    )
    (net (code "65") (name "Net-(IRD1L-PadOUT)") (class "Default")
      (node (ref "IRD1L") (pin "OUT") (pinfunction "OUT_OUT") (pintype "bidirectional"))
      (node (ref "IRR1L") (pin "2") (pinfunction "2_2") (pintype "passive"))
    )
    (net (code "66") (name "Net-(IRD1R-PadOUT)") (class "Default")
      (node (ref "IRD1R") (pin "OUT") (pinfunction "OUT_OUT") (pintype "bidirectional"))
      (node (ref "IRR1R") (pin "2") (pinfunction "2_2") (pintype "passive"))
    )
    (net (code "67") (name "Net-(IRD2L-PadOUT)") (class "Default")
      (node (ref "IRD2L") (pin "OUT") (pinfunction "OUT_OUT") (pintype "bidirectional"))
      (node (ref "IRR2L") (pin "2") (pinfunction "2_2") (pintype "passive"))
    )
    (net (code "68") (name "Net-(IRD2R-PadOUT)") (class "Default")
      (node (ref "IRD2R") (pin "OUT") (pinfunction "OUT_OUT") (pintype "bidirectional"))
      (node (ref "IRR2R") (pin "2") (pinfunction "2_2") (pintype "passive"))
    )
    (net (code "69") (name "Net-(IRD3L-PadOUT)") (class "Default")
      (node (ref "IRD3L") (pin "OUT") (pinfunction "OUT_OUT") (pintype "bidirectional"))
      (node (ref "IRR3L") (pin "2") (pinfunction "2_2") (pintype "passive"))
    )
    (net (code "70") (name "Net-(IRD3R-PadOUT)") (class "Default")
      (node (ref "IRD3R") (pin "OUT") (pinfunction "OUT_OUT") (pintype "bidirectional"))
      (node (ref "IRR3R") (pin "2") (pinfunction "2_2") (pintype "passive"))
    )
    (net (code "71") (name "Net-(IRD4L-PadOUT)") (class "Default")
      (node (ref "IRD4L") (pin "OUT") (pinfunction "OUT_OUT") (pintype "bidirectional"))
      (node (ref "IRR4L") (pin "2") (pinfunction "2_2") (pintype "passive"))
    )
    (net (code "72") (name "Net-(IRD4R-PadOUT)") (class "Default")
      (node (ref "IRD4R") (pin "OUT") (pinfunction "OUT_OUT") (pintype "bidirectional"))
      (node (ref "IRR4R") (pin "2") (pinfunction "2_2") (pintype "passive"))
    )
    (net (code "73") (name "Net-(IRD5L-PadOUT)") (class "Default")
      (node (ref "IRD5L") (pin "OUT") (pinfunction "OUT_OUT") (pintype "bidirectional"))
      (node (ref "IRR5L") (pin "1") (pinfunction "1_1") (pintype "passive"))
    )
    (net (code "74") (name "Net-(IRD5R-PadOUT)") (class "Default")
      (node (ref "IRD5R") (pin "OUT") (pinfunction "OUT_OUT") (pintype "bidirectional"))
      (node (ref "IRR5R") (pin "1") (pinfunction "1_1") (pintype "passive"))
    )
    (net (code "75") (name "Net-(IRD6L-PadOUT)") (class "Default")
      (node (ref "IRD6L") (pin "OUT") (pinfunction "OUT_OUT") (pintype "bidirectional"))
      (node (ref "IRR6L") (pin "2") (pinfunction "2_2") (pintype "passive"))
    )
    (net (code "76") (name "Net-(IRD6R-PadOUT)") (class "Default")
      (node (ref "IRD6R") (pin "OUT") (pinfunction "OUT_OUT") (pintype "bidirectional"))
      (node (ref "IRR6R") (pin "2") (pinfunction "2_2") (pintype "passive"))
    )
    (net (code "77") (name "Net-(IRD7L-PadOUT)") (class "Default")
      (node (ref "IRD7L") (pin "OUT") (pinfunction "OUT_OUT") (pintype "bidirectional"))
      (node (ref "IRR7L") (pin "2") (pinfunction "2_2") (pintype "passive"))
    )
    (net (code "78") (name "Net-(IRD7R-PadOUT)") (class "Default")
      (node (ref "IRD7R") (pin "OUT") (pinfunction "OUT_OUT") (pintype "bidirectional"))
      (node (ref "IRR7R") (pin "2") (pinfunction "2_2") (pintype "passive"))
    )
    (net (code "79") (name "Net-(IRDP-PadOUT)") (class "Default")
      (node (ref "IRDP") (pin "OUT") (pinfunction "OUT_OUT") (pintype "bidirectional"))
      (node (ref "IRR4R1") (pin "1") (pinfunction "1_1") (pintype "passive"))
    )
    (net (code "80") (name "Net-(LT-AT-PB5)") (class "Default")
      (node (ref "LT-AT") (pin "19") (pinfunction "PB5_19") (pintype "bidirectional"))
      (node (ref "LT-R2") (pin "2") (pinfunction "2_2") (pintype "passive"))
    )
    (net (code "81") (name "Net-(LT-AT-PB6)") (class "Default")
      (node (ref "LT-AT") (pin "9") (pinfunction "PB6_9") (pintype "bidirectional"))
      (node (ref "LT-ATC1") (pin "2") (pinfunction "2_2") (pintype "passive"))
      (node (ref "LT-CR") (pin "2") (pinfunction "2_2") (pintype "passive"))
    )
    (net (code "82") (name "Net-(LT-AT-PB7)") (class "Default")
      (node (ref "LT-AT") (pin "10") (pinfunction "PB7_10") (pintype "bidirectional"))
      (node (ref "LT-ATC2") (pin "2") (pinfunction "2_2") (pintype "passive"))
      (node (ref "LT-CR") (pin "1") (pinfunction "1_1") (pintype "passive"))
    )
    (net (code "83") (name "Net-(LT-AT-PC6)") (class "Default")
      (node (ref "LT-AT") (pin "1") (pinfunction "PC6_1") (pintype "bidirectional"))
      (node (ref "LT-BTN") (pin "A") (pinfunction "A_A") (pintype "passive"))
      (node (ref "LT-R1") (pin "2") (pinfunction "2_2") (pintype "passive"))
    )
    (net (code "84") (name "Net-(LT-LED-PadA)") (class "Default")
      (node (ref "LT-LED") (pin "A") (pinfunction "A_A") (pintype "passive"))
      (node (ref "LT-R2") (pin "1") (pinfunction "1_1") (pintype "passive"))
    )
    (net (code "85") (name "VCC") (class "Default")
      (node (ref "IR-RC2") (pin "-") (pinfunction "-_-") (pintype "passive"))
      (node (ref "IR-TRAN") (pin "1") (pinfunction "VI_1") (pintype "input"))
      (node (ref "LT-RC1") (pin "-") (pinfunction "-_-") (pintype "passive"))
      (node (ref "LT-TRAN") (pin "1") (pinfunction "VI_1") (pintype "input"))
      (node (ref "VEL") (pin "2") (pinfunction "KL_2") (pintype "passive"))
    )
    (net (code "86") (name "unconnected-(CS-AT-PB0-Pad14)") (class "Default")
      (node (ref "CS-AT") (pin "14") (pinfunction "PB0_14") (pintype "bidirectional"))
    )
    (net (code "87") (name "unconnected-(CS-AT-PB1-Pad15)") (class "Default")
      (node (ref "CS-AT") (pin "15") (pinfunction "PB1_15") (pintype "bidirectional"))
    )
    (net (code "88") (name "unconnected-(CS-AT-PB2-Pad16)") (class "Default")
      (node (ref "CS-AT") (pin "16") (pinfunction "PB2_16") (pintype "bidirectional"))
    )
    (net (code "89") (name "unconnected-(CS-AT-PB3-Pad17)") (class "Default")
      (node (ref "CS-AT") (pin "17") (pinfunction "PB3_17") (pintype "bidirectional"))
    )
    (net (code "90") (name "unconnected-(CS-AT-PB4-Pad18)") (class "Default")
      (node (ref "CS-AT") (pin "18") (pinfunction "PB4_18") (pintype "bidirectional"))
    )
    (net (code "91") (name "unconnected-(CS-AT-PC0-Pad23)") (class "Default")
      (node (ref "CS-AT") (pin "23") (pinfunction "PC0_23") (pintype "bidirectional"))
    )
    (net (code "92") (name "unconnected-(CS-AT-PC1-Pad24)") (class "Default")
      (node (ref "CS-AT") (pin "24") (pinfunction "PC1_24") (pintype "bidirectional"))
    )
    (net (code "93") (name "unconnected-(CS-AT-PC2-Pad25)") (class "Default")
      (node (ref "CS-AT") (pin "25") (pinfunction "PC2_25") (pintype "bidirectional"))
    )
    (net (code "94") (name "unconnected-(CS-AT-PC3-Pad26)") (class "Default")
      (node (ref "CS-AT") (pin "26") (pinfunction "PC3_26") (pintype "bidirectional"))
    )
    (net (code "95") (name "unconnected-(CS-AT-PD2-Pad4)") (class "Default")
      (node (ref "CS-AT") (pin "4") (pinfunction "PD2_4") (pintype "bidirectional"))
    )
    (net (code "96") (name "unconnected-(CS-AT-PD3-Pad5)") (class "Default")
      (node (ref "CS-AT") (pin "5") (pinfunction "PD3_5") (pintype "bidirectional"))
    )
    (net (code "97") (name "unconnected-(CS-AT-PD4-Pad6)") (class "Default")
      (node (ref "CS-AT") (pin "6") (pinfunction "PD4_6") (pintype "bidirectional"))
    )
    (net (code "98") (name "unconnected-(CS-AT-PD5-Pad11)") (class "Default")
      (node (ref "CS-AT") (pin "11") (pinfunction "PD5_11") (pintype "bidirectional"))
    )
    (net (code "99") (name "unconnected-(CS-AT-PD6-Pad12)") (class "Default")
      (node (ref "CS-AT") (pin "12") (pinfunction "PD6_12") (pintype "bidirectional"))
    )
    (net (code "100") (name "unconnected-(CS-AT-PD7-Pad13)") (class "Default")
      (node (ref "CS-AT") (pin "13") (pinfunction "PD7_13") (pintype "bidirectional"))
    )
    (net (code "101") (name "unconnected-(CS-BTN-PadA1)") (class "Default")
      (node (ref "CS-BTN") (pin "A1") (pinfunction "A1_A1") (pintype "passive"))
    )
    (net (code "102") (name "unconnected-(IR-AT-PB0-Pad14)") (class "Default")
      (node (ref "IR-AT") (pin "14") (pinfunction "PB0_14") (pintype "bidirectional"))
    )
    (net (code "103") (name "unconnected-(IR-AT-PB1-Pad15)") (class "Default")
      (node (ref "IR-AT") (pin "15") (pinfunction "PB1_15") (pintype "bidirectional"))
    )
    (net (code "104") (name "unconnected-(IR-AT-PB2-Pad16)") (class "Default")
      (node (ref "IR-AT") (pin "16") (pinfunction "PB2_16") (pintype "bidirectional"))
    )
    (net (code "105") (name "unconnected-(IR-AT-PB3-Pad17)") (class "Default")
      (node (ref "IR-AT") (pin "17") (pinfunction "PB3_17") (pintype "bidirectional"))
    )
    (net (code "106") (name "unconnected-(IR-AT-PB4-Pad18)") (class "Default")
      (node (ref "IR-AT") (pin "18") (pinfunction "PB4_18") (pintype "bidirectional"))
    )
    (net (code "107") (name "unconnected-(IR-AT-PC3-Pad26)") (class "Default")
      (node (ref "IR-AT") (pin "26") (pinfunction "PC3_26") (pintype "bidirectional"))
    )
    (net (code "108") (name "unconnected-(IR-AT-PC4-Pad27)") (class "Default")
      (node (ref "IR-AT") (pin "27") (pinfunction "PC4_27") (pintype "bidirectional"))
    )
    (net (code "109") (name "unconnected-(IR-AT-PC5-Pad28)") (class "Default")
      (node (ref "IR-AT") (pin "28") (pinfunction "PC5_28") (pintype "bidirectional"))
    )
    (net (code "110") (name "unconnected-(IR-BTN-PadA1)") (class "Default")
      (node (ref "IR-BTN") (pin "A1") (pinfunction "A1_A1") (pintype "passive"))
    )
    (net (code "111") (name "unconnected-(IR-MULT-LA-D0-Pad4)") (class "Default")
      (node (ref "IR-MULT-L") (pin "4") (pinfunction "D0_4") (pintype "input"))
    )
    (net (code "112") (name "unconnected-(IR-MULT-LA-W-Pad6)") (class "Default")
      (node (ref "IR-MULT-L") (pin "6") (pinfunction "W_6") (pintype "output"))
    )
    (net (code "113") (name "unconnected-(IR-MULT-RA-D0-Pad4)") (class "Default")
      (node (ref "IR-MULT-R") (pin "4") (pinfunction "D0_4") (pintype "input"))
    )
    (net (code "114") (name "unconnected-(IR-MULT-RA-W-Pad6)") (class "Default")
      (node (ref "IR-MULT-R") (pin "6") (pinfunction "W_6") (pintype "output"))
    )
    (net (code "115") (name "unconnected-(LT-AT-PB0-Pad14)") (class "Default")
      (node (ref "LT-AT") (pin "14") (pinfunction "PB0_14") (pintype "bidirectional"))
    )
    (net (code "116") (name "unconnected-(LT-AT-PB1-Pad15)") (class "Default")
      (node (ref "LT-AT") (pin "15") (pinfunction "PB1_15") (pintype "bidirectional"))
    )
    (net (code "117") (name "unconnected-(LT-AT-PB2-Pad16)") (class "Default")
      (node (ref "LT-AT") (pin "16") (pinfunction "PB2_16") (pintype "bidirectional"))
    )
    (net (code "118") (name "unconnected-(LT-AT-PB3-Pad17)") (class "Default")
      (node (ref "LT-AT") (pin "17") (pinfunction "PB3_17") (pintype "bidirectional"))
    )
    (net (code "119") (name "unconnected-(LT-AT-PB4-Pad18)") (class "Default")
      (node (ref "LT-AT") (pin "18") (pinfunction "PB4_18") (pintype "bidirectional"))
    )
    (net (code "120") (name "unconnected-(LT-AT-PC2-Pad25)") (class "Default")
      (node (ref "LT-AT") (pin "25") (pinfunction "PC2_25") (pintype "bidirectional"))
    )
    (net (code "121") (name "unconnected-(LT-AT-PC3-Pad26)") (class "Default")
      (node (ref "LT-AT") (pin "26") (pinfunction "PC3_26") (pintype "bidirectional"))
    )
    (net (code "122") (name "unconnected-(LT-AT-PC4-Pad27)") (class "Default")
      (node (ref "LT-AT") (pin "27") (pinfunction "PC4_27") (pintype "bidirectional"))
    )
    (net (code "123") (name "unconnected-(LT-AT-PC5-Pad28)") (class "Default")
      (node (ref "LT-AT") (pin "28") (pinfunction "PC5_28") (pintype "bidirectional"))
    )
    (net (code "124") (name "unconnected-(LT-BTN-PadA1)") (class "Default")
      (node (ref "LT-BTN") (pin "A1") (pinfunction "A1_A1") (pintype "passive"))
    )
    (net (code "125") (name "unconnected-(LT-MULT-1A-D0-Pad4)") (class "Default")
      (node (ref "LT-MULT-1") (pin "4") (pinfunction "D0_4") (pintype "input"))
    )
    (net (code "126") (name "unconnected-(LT-MULT-1A-D7-Pad12)") (class "Default")
      (node (ref "LT-MULT-1") (pin "12") (pinfunction "D7_12") (pintype "input"))
    )
    (net (code "127") (name "unconnected-(LT-MULT-1A-W-Pad6)") (class "Default")
      (node (ref "LT-MULT-1") (pin "6") (pinfunction "W_6") (pintype "output"))
    )
    (net (code "128") (name "unconnected-(LT-MULT-2A-D0-Pad4)") (class "Default")
      (node (ref "LT-MULT-2") (pin "4") (pinfunction "D0_4") (pintype "input"))
    )
    (net (code "129") (name "unconnected-(LT-MULT-2A-D7-Pad12)") (class "Default")
      (node (ref "LT-MULT-2") (pin "12") (pinfunction "D7_12") (pintype "input"))
    )
    (net (code "130") (name "unconnected-(LT-MULT-2A-W-Pad6)") (class "Default")
      (node (ref "LT-MULT-2") (pin "6") (pinfunction "W_6") (pintype "output"))
    )
  )
)
